# Analog_PID_Controller.net
KiCad netlist of a schematic drawn in EAGLE
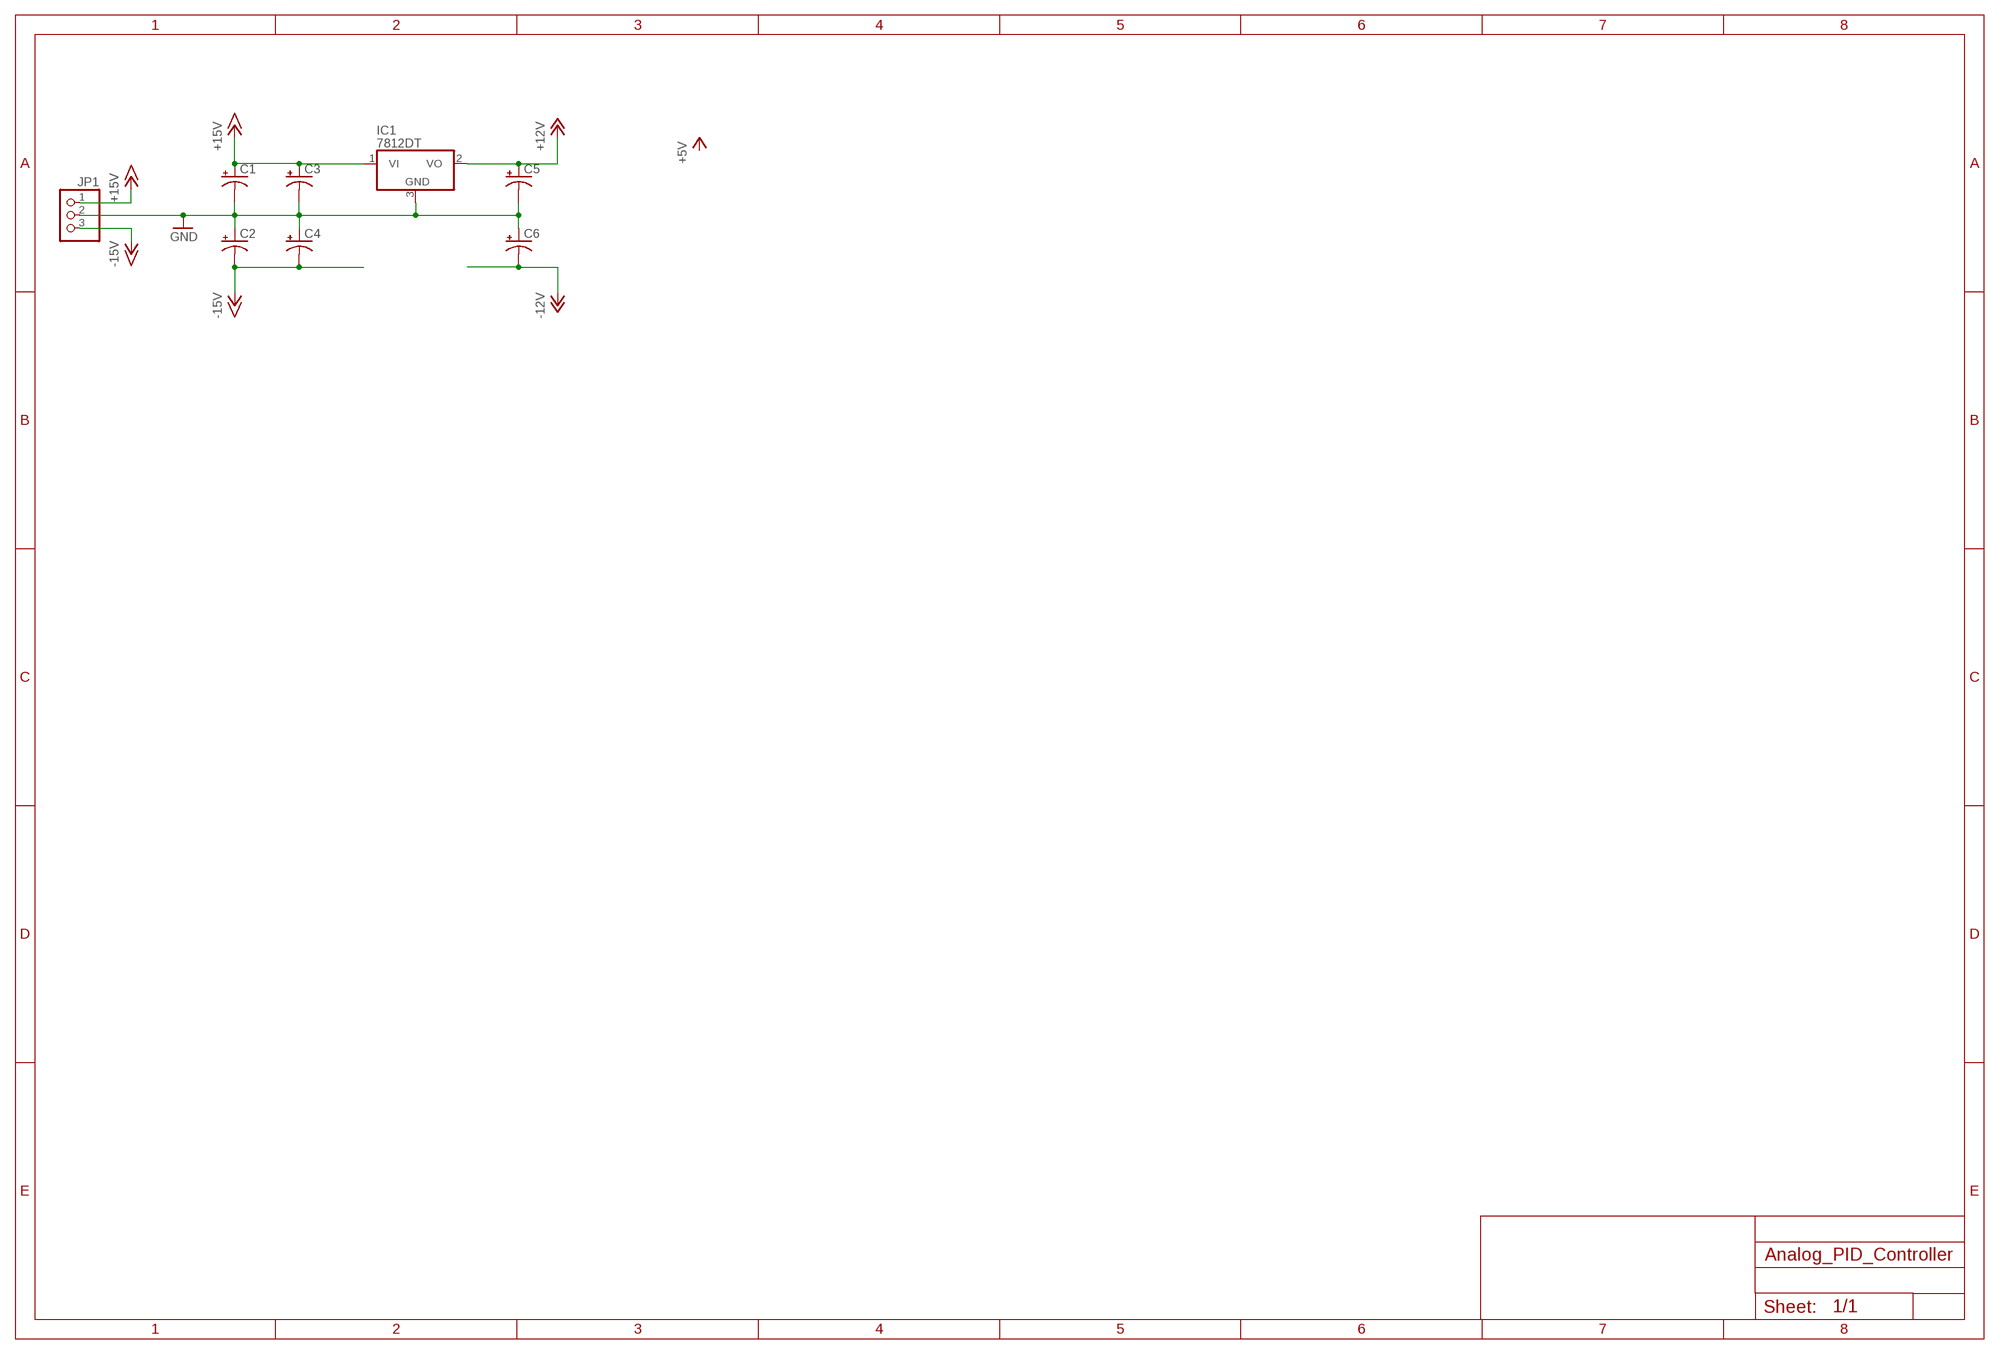
[diagram p0: schematic, sheet 1]

(export (version "E")
  (design (tool "Eeschema 10.0.6"))
  (components
    (comp (ref "C1")
      (value "CPOL-USD")
      (footprint "eagle-import:PANASONIC_D")
      (libsource (lib "eagle-import") (part "CPOL-USD"))
    )
    (comp (ref "C2")
      (value "CPOL-USD")
      (footprint "eagle-import:PANASONIC_D")
      (libsource (lib "eagle-import") (part "CPOL-USD"))
    )
    (comp (ref "C3")
      (value "CPOL-USD")
      (footprint "eagle-import:PANASONIC_D")
      (libsource (lib "eagle-import") (part "CPOL-USD"))
    )
    (comp (ref "C4")
      (value "CPOL-USD")
      (footprint "eagle-import:PANASONIC_D")
      (libsource (lib "eagle-import") (part "CPOL-USD"))
    )
    (comp (ref "C5")
      (value "CPOL-USD")
      (footprint "eagle-import:PANASONIC_D")
      (libsource (lib "eagle-import") (part "CPOL-USD"))
    )
    (comp (ref "C6")
      (value "CPOL-USD")
      (footprint "eagle-import:PANASONIC_D")
      (libsource (lib "eagle-import") (part "CPOL-USD"))
    )
    (comp (ref "IC1")
      (value "7812DT")
      (footprint "eagle-import:TO252")
      (libsource (lib "eagle-import") (part "78DT12"))
    )
    (comp (ref "JP1")
      (value "PINHD-1X3/90")
      (footprint "eagle-import:1X03_90")
      (libsource (lib "eagle-import") (part "PINHD-1X3/90"))
    )
  )
  (nets
    (net (code "2") (name "+12V") (class "Default")
      (node (ref "C5") (pin "+") (pinfunction "+_+") (pintype "passive"))
      (node (ref "IC1") (pin "2") (pinfunction "VO_2") (pintype "passive"))
    )
    (net (code "3") (name "+15V") (class "Default")
      (node (ref "C1") (pin "+") (pinfunction "+_+") (pintype "passive"))
      (node (ref "C3") (pin "+") (pinfunction "+_+") (pintype "passive"))
      (node (ref "IC1") (pin "1") (pinfunction "VI_1") (pintype "input"))
      (node (ref "JP1") (pin "1") (pinfunction "1_1") (pintype "passive"))
    )
    (net (code "4") (name "-12V") (class "Default")
      (node (ref "C6") (pin "-") (pinfunction "-_-") (pintype "passive"))
    )
    (net (code "5") (name "-15V") (class "Default")
      (node (ref "C2") (pin "-") (pinfunction "-_-") (pintype "passive"))
      (node (ref "C4") (pin "-") (pinfunction "-_-") (pintype "passive"))
      (node (ref "JP1") (pin "3") (pinfunction "3_3") (pintype "passive"))
    )
    (net (code "6") (name "GND") (class "Default")
      (node (ref "C1") (pin "-") (pinfunction "-_-") (pintype "passive"))
      (node (ref "C2") (pin "+") (pinfunction "+_+") (pintype "passive"))
      (node (ref "C3") (pin "-") (pinfunction "-_-") (pintype "passive"))
      (node (ref "C4") (pin "+") (pinfunction "+_+") (pintype "passive"))
      (node (ref "C5") (pin "-") (pinfunction "-_-") (pintype "passive"))
      (node (ref "C6") (pin "+") (pinfunction "+_+") (pintype "passive"))
      (node (ref "IC1") (pin "3") (pinfunction "GND_3") (pintype "passive"))
      (node (ref "JP1") (pin "2") (pinfunction "2_2") (pintype "passive"))
    )
  )
)
